# Hall.net
KiCad netlist of a schematic drawn in Altium Designer
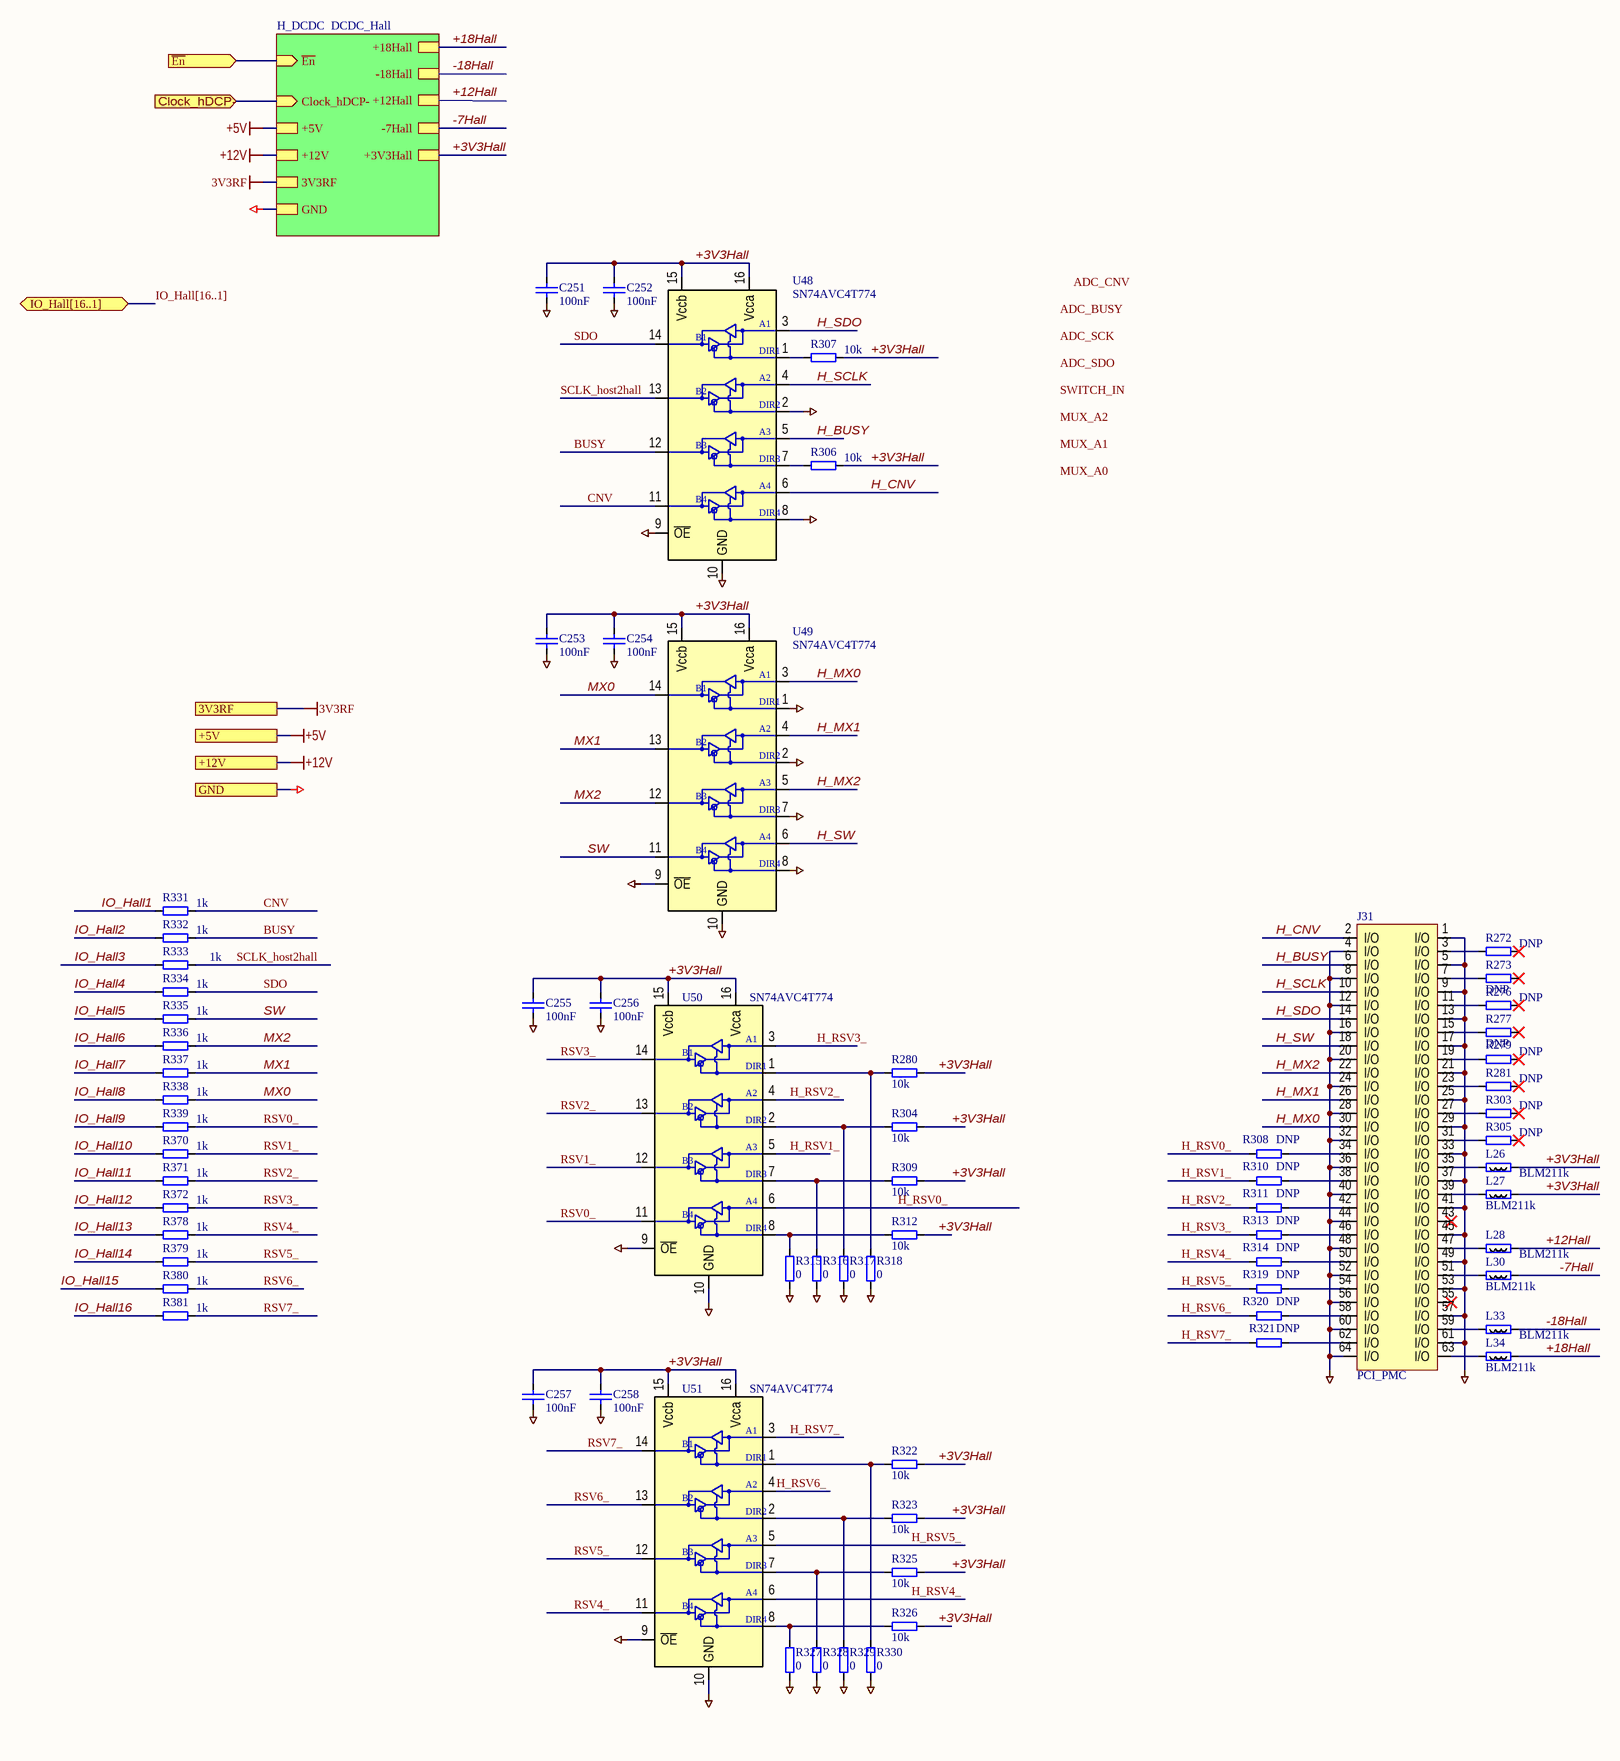
[diagram p0: Hall.SchDoc]

(export (version "E")
  (design (tool "Eeschema 10.0.6"))
  (components
    (comp (ref "C251")
      (value "100nF")
      (footprint "SMD0805CAP")
      (description "Чип конденсатор 0805")
      (fields (field (name "VOLTAGE") "25V") (field (name "TOLERANCE") "20%"))
      (libsource (lib "DDSintLib") (part "C0805"))
    )
    (comp (ref "C252")
      (value "100nF")
      (footprint "SMD0805CAP")
      (description "Чип конденсатор 0805")
      (fields (field (name "VOLTAGE") "25V") (field (name "TOLERANCE") "20%"))
      (libsource (lib "DDSintLib") (part "C0805"))
    )
    (comp (ref "C253")
      (value "100nF")
      (footprint "SMD0805CAP")
      (description "Чип конденсатор 0805")
      (fields (field (name "VOLTAGE") "25V") (field (name "TOLERANCE") "20%"))
      (libsource (lib "DDSintLib") (part "C0805"))
    )
    (comp (ref "C254")
      (value "100nF")
      (footprint "SMD0805CAP")
      (description "Чип конденсатор 0805")
      (fields (field (name "VOLTAGE") "25V") (field (name "TOLERANCE") "20%"))
      (libsource (lib "DDSintLib") (part "C0805"))
    )
    (comp (ref "C255")
      (value "100nF")
      (footprint "SMD0805CAP")
      (description "Чип конденсатор 0805")
      (fields (field (name "VOLTAGE") "25V") (field (name "TOLERANCE") "20%"))
      (libsource (lib "DDSintLib") (part "C0805"))
    )
    (comp (ref "C256")
      (value "100nF")
      (footprint "SMD0805CAP")
      (description "Чип конденсатор 0805")
      (fields (field (name "VOLTAGE") "25V") (field (name "TOLERANCE") "20%"))
      (libsource (lib "DDSintLib") (part "C0805"))
    )
    (comp (ref "C257")
      (value "100nF")
      (footprint "SMD0805CAP")
      (description "Чип конденсатор 0805")
      (fields (field (name "VOLTAGE") "25V") (field (name "TOLERANCE") "20%"))
      (libsource (lib "DDSintLib") (part "C0805"))
    )
    (comp (ref "C258")
      (value "100nF")
      (footprint "SMD0805CAP")
      (description "Чип конденсатор 0805")
      (fields (field (name "VOLTAGE") "25V") (field (name "TOLERANCE") "20%"))
      (libsource (lib "DDSintLib") (part "C0805"))
    )
    (comp (ref "J31")
      (value "PCI_PMC")
      (footprint "TYCO_120521-1")
      (description "PCI Mezzanine Connector; IEEE 1386 MainBoard")
      (libsource (lib "DDSintLib") (part "PCI_PMC_M"))
    )
    (comp (ref "L26")
      (value "BLM211k")
      (footprint "RESC2012X50N")
      (description "SMD Ferrite bead 0805")
      (libsource (lib "DDSintLib") (part "BLM21"))
    )
    (comp (ref "L27")
      (value "BLM211k")
      (footprint "RESC2012X50N")
      (description "SMD Ferrite bead 0805")
      (libsource (lib "DDSintLib") (part "BLM21"))
    )
    (comp (ref "L28")
      (value "BLM211k")
      (footprint "RESC2012X50N")
      (description "SMD Ferrite bead 0805")
      (libsource (lib "DDSintLib") (part "BLM21"))
    )
    (comp (ref "L30")
      (value "BLM211k")
      (footprint "RESC2012X50N")
      (description "SMD Ferrite bead 0805")
      (libsource (lib "DDSintLib") (part "BLM21"))
    )
    (comp (ref "L33")
      (value "BLM211k")
      (footprint "RESC2012X50N")
      (description "SMD Ferrite bead 0805")
      (libsource (lib "DDSintLib") (part "BLM21"))
    )
    (comp (ref "L34")
      (value "BLM211k")
      (footprint "RESC2012X50N")
      (description "SMD Ferrite bead 0805")
      (libsource (lib "DDSintLib") (part "BLM21"))
    )
    (comp (ref "R272")
      (value "DNP")
      (footprint "SMD0805RES")
      (description "Чип резистор 0805")
      (fields (field (name "TOLERANCE") "1%"))
      (libsource (lib "DDSintLib") (part "R0805"))
    )
    (comp (ref "R273")
      (value "DNP")
      (footprint "SMD0805RES")
      (description "Чип резистор 0805")
      (fields (field (name "TOLERANCE") "1%"))
      (libsource (lib "DDSintLib") (part "R0805"))
    )
    (comp (ref "R276")
      (value "DNP")
      (footprint "SMD0805RES")
      (description "Чип резистор 0805")
      (fields (field (name "TOLERANCE") "1%"))
      (libsource (lib "DDSintLib") (part "R0805"))
    )
    (comp (ref "R277")
      (value "DNP")
      (footprint "SMD0805RES")
      (description "Чип резистор 0805")
      (fields (field (name "TOLERANCE") "1%"))
      (libsource (lib "DDSintLib") (part "R0805"))
    )
    (comp (ref "R279")
      (value "DNP")
      (footprint "SMD0805RES")
      (description "Чип резистор 0805")
      (fields (field (name "TOLERANCE") "1%"))
      (libsource (lib "DDSintLib") (part "R0805"))
    )
    (comp (ref "R280")
      (value "10k")
      (footprint "SMD0805RES")
      (description "Чип резистор 0805")
      (fields (field (name "TOLERANCE") "1%"))
      (libsource (lib "DDSintLib") (part "R0805"))
    )
    (comp (ref "R281")
      (value "DNP")
      (footprint "SMD0805RES")
      (description "Чип резистор 0805")
      (fields (field (name "TOLERANCE") "1%"))
      (libsource (lib "DDSintLib") (part "R0805"))
    )
    (comp (ref "R303")
      (value "DNP")
      (footprint "SMD0805RES")
      (description "Чип резистор 0805")
      (fields (field (name "TOLERANCE") "1%"))
      (libsource (lib "DDSintLib") (part "R0805"))
    )
    (comp (ref "R304")
      (value "10k")
      (footprint "SMD0805RES")
      (description "Чип резистор 0805")
      (fields (field (name "TOLERANCE") "1%"))
      (libsource (lib "DDSintLib") (part "R0805"))
    )
    (comp (ref "R305")
      (value "DNP")
      (footprint "SMD0805RES")
      (description "Чип резистор 0805")
      (fields (field (name "TOLERANCE") "1%"))
      (libsource (lib "DDSintLib") (part "R0805"))
    )
    (comp (ref "R306")
      (value "10k")
      (footprint "SMD0805RES")
      (description "Чип резистор 0805")
      (fields (field (name "TOLERANCE") "1%"))
      (libsource (lib "DDSintLib") (part "R0805"))
    )
    (comp (ref "R307")
      (value "10k")
      (footprint "SMD0805RES")
      (description "Чип резистор 0805")
      (fields (field (name "TOLERANCE") "1%"))
      (libsource (lib "DDSintLib") (part "R0805"))
    )
    (comp (ref "R308")
      (value "DNP")
      (footprint "SMD0805RES")
      (description "Чип резистор 0805")
      (fields (field (name "TOLERANCE") "1%"))
      (libsource (lib "DDSintLib") (part "R0805"))
    )
    (comp (ref "R309")
      (value "10k")
      (footprint "SMD0805RES")
      (description "Чип резистор 0805")
      (fields (field (name "TOLERANCE") "1%"))
      (libsource (lib "DDSintLib") (part "R0805"))
    )
    (comp (ref "R310")
      (value "DNP")
      (footprint "SMD0805RES")
      (description "Чип резистор 0805")
      (fields (field (name "TOLERANCE") "1%"))
      (libsource (lib "DDSintLib") (part "R0805"))
    )
    (comp (ref "R311")
      (value "DNP")
      (footprint "SMD0805RES")
      (description "Чип резистор 0805")
      (fields (field (name "TOLERANCE") "1%"))
      (libsource (lib "DDSintLib") (part "R0805"))
    )
    (comp (ref "R312")
      (value "10k")
      (footprint "SMD0805RES")
      (description "Чип резистор 0805")
      (fields (field (name "TOLERANCE") "1%"))
      (libsource (lib "DDSintLib") (part "R0805"))
    )
    (comp (ref "R313")
      (value "DNP")
      (footprint "SMD0805RES")
      (description "Чип резистор 0805")
      (fields (field (name "TOLERANCE") "1%"))
      (libsource (lib "DDSintLib") (part "R0805"))
    )
    (comp (ref "R314")
      (value "DNP")
      (footprint "SMD0805RES")
      (description "Чип резистор 0805")
      (fields (field (name "TOLERANCE") "1%"))
      (libsource (lib "DDSintLib") (part "R0805"))
    )
    (comp (ref "R315")
      (value "0")
      (footprint "SMD0805RES")
      (description "Чип резистор 0805")
      (fields (field (name "TOLERANCE") "1%"))
      (libsource (lib "DDSintLib") (part "R0805"))
    )
    (comp (ref "R316")
      (value "0")
      (footprint "SMD0805RES")
      (description "Чип резистор 0805")
      (fields (field (name "TOLERANCE") "1%"))
      (libsource (lib "DDSintLib") (part "R0805"))
    )
    (comp (ref "R317")
      (value "0")
      (footprint "SMD0805RES")
      (description "Чип резистор 0805")
      (fields (field (name "TOLERANCE") "1%"))
      (libsource (lib "DDSintLib") (part "R0805"))
    )
    (comp (ref "R318")
      (value "0")
      (footprint "SMD0805RES")
      (description "Чип резистор 0805")
      (fields (field (name "TOLERANCE") "1%"))
      (libsource (lib "DDSintLib") (part "R0805"))
    )
    (comp (ref "R319")
      (value "DNP")
      (footprint "SMD0805RES")
      (description "Чип резистор 0805")
      (fields (field (name "TOLERANCE") "1%"))
      (libsource (lib "DDSintLib") (part "R0805"))
    )
    (comp (ref "R320")
      (value "DNP")
      (footprint "SMD0805RES")
      (description "Чип резистор 0805")
      (fields (field (name "TOLERANCE") "1%"))
      (libsource (lib "DDSintLib") (part "R0805"))
    )
    (comp (ref "R321")
      (value "DNP")
      (footprint "SMD0805RES")
      (description "Чип резистор 0805")
      (fields (field (name "TOLERANCE") "1%"))
      (libsource (lib "DDSintLib") (part "R0805"))
    )
    (comp (ref "R322")
      (value "10k")
      (footprint "SMD0805RES")
      (description "Чип резистор 0805")
      (fields (field (name "TOLERANCE") "1%"))
      (libsource (lib "DDSintLib") (part "R0805"))
    )
    (comp (ref "R323")
      (value "10k")
      (footprint "SMD0805RES")
      (description "Чип резистор 0805")
      (fields (field (name "TOLERANCE") "1%"))
      (libsource (lib "DDSintLib") (part "R0805"))
    )
    (comp (ref "R325")
      (value "10k")
      (footprint "SMD0805RES")
      (description "Чип резистор 0805")
      (fields (field (name "TOLERANCE") "1%"))
      (libsource (lib "DDSintLib") (part "R0805"))
    )
    (comp (ref "R326")
      (value "10k")
      (footprint "SMD0805RES")
      (description "Чип резистор 0805")
      (fields (field (name "TOLERANCE") "1%"))
      (libsource (lib "DDSintLib") (part "R0805"))
    )
    (comp (ref "R327")
      (value "0")
      (footprint "SMD0805RES")
      (description "Чип резистор 0805")
      (fields (field (name "TOLERANCE") "1%"))
      (libsource (lib "DDSintLib") (part "R0805"))
    )
    (comp (ref "R328")
      (value "0")
      (footprint "SMD0805RES")
      (description "Чип резистор 0805")
      (fields (field (name "TOLERANCE") "1%"))
      (libsource (lib "DDSintLib") (part "R0805"))
    )
    (comp (ref "R329")
      (value "0")
      (footprint "SMD0805RES")
      (description "Чип резистор 0805")
      (fields (field (name "TOLERANCE") "1%"))
      (libsource (lib "DDSintLib") (part "R0805"))
    )
    (comp (ref "R330")
      (value "0")
      (footprint "SMD0805RES")
      (description "Чип резистор 0805")
      (fields (field (name "TOLERANCE") "1%"))
      (libsource (lib "DDSintLib") (part "R0805"))
    )
    (comp (ref "R331")
      (value "1k")
      (footprint "SMD0805RES")
      (description "Чип резистор 0805")
      (fields (field (name "TOLERANCE") "1%"))
      (libsource (lib "DDSintLib") (part "R0805"))
    )
    (comp (ref "R332")
      (value "1k")
      (footprint "SMD0805RES")
      (description "Чип резистор 0805")
      (fields (field (name "TOLERANCE") "1%"))
      (libsource (lib "DDSintLib") (part "R0805"))
    )
    (comp (ref "R333")
      (value "1k")
      (footprint "SMD0805RES")
      (description "Чип резистор 0805")
      (fields (field (name "TOLERANCE") "1%"))
      (libsource (lib "DDSintLib") (part "R0805"))
    )
    (comp (ref "R334")
      (value "1k")
      (footprint "SMD0805RES")
      (description "Чип резистор 0805")
      (fields (field (name "TOLERANCE") "1%"))
      (libsource (lib "DDSintLib") (part "R0805"))
    )
    (comp (ref "R335")
      (value "1k")
      (footprint "SMD0805RES")
      (description "Чип резистор 0805")
      (fields (field (name "TOLERANCE") "1%"))
      (libsource (lib "DDSintLib") (part "R0805"))
    )
    (comp (ref "R336")
      (value "1k")
      (footprint "SMD0805RES")
      (description "Чип резистор 0805")
      (fields (field (name "TOLERANCE") "1%"))
      (libsource (lib "DDSintLib") (part "R0805"))
    )
    (comp (ref "R337")
      (value "1k")
      (footprint "SMD0805RES")
      (description "Чип резистор 0805")
      (fields (field (name "TOLERANCE") "1%"))
      (libsource (lib "DDSintLib") (part "R0805"))
    )
    (comp (ref "R338")
      (value "1k")
      (footprint "SMD0805RES")
      (description "Чип резистор 0805")
      (fields (field (name "TOLERANCE") "1%"))
      (libsource (lib "DDSintLib") (part "R0805"))
    )
    (comp (ref "R339")
      (value "1k")
      (footprint "SMD0805RES")
      (description "Чип резистор 0805")
      (fields (field (name "TOLERANCE") "1%"))
      (libsource (lib "DDSintLib") (part "R0805"))
    )
    (comp (ref "R370")
      (value "1k")
      (footprint "SMD0805RES")
      (description "Чип резистор 0805")
      (fields (field (name "TOLERANCE") "1%"))
      (libsource (lib "DDSintLib") (part "R0805"))
    )
    (comp (ref "R371")
      (value "1k")
      (footprint "SMD0805RES")
      (description "Чип резистор 0805")
      (fields (field (name "TOLERANCE") "1%"))
      (libsource (lib "DDSintLib") (part "R0805"))
    )
    (comp (ref "R372")
      (value "1k")
      (footprint "SMD0805RES")
      (description "Чип резистор 0805")
      (fields (field (name "TOLERANCE") "1%"))
      (libsource (lib "DDSintLib") (part "R0805"))
    )
    (comp (ref "R378")
      (value "1k")
      (footprint "SMD0805RES")
      (description "Чип резистор 0805")
      (fields (field (name "TOLERANCE") "1%"))
      (libsource (lib "DDSintLib") (part "R0805"))
    )
    (comp (ref "R379")
      (value "1k")
      (footprint "SMD0805RES")
      (description "Чип резистор 0805")
      (fields (field (name "TOLERANCE") "1%"))
      (libsource (lib "DDSintLib") (part "R0805"))
    )
    (comp (ref "R380")
      (value "1k")
      (footprint "SMD0805RES")
      (description "Чип резистор 0805")
      (fields (field (name "TOLERANCE") "1%"))
      (libsource (lib "DDSintLib") (part "R0805"))
    )
    (comp (ref "R381")
      (value "1k")
      (footprint "SMD0805RES")
      (description "Чип резистор 0805")
      (fields (field (name "TOLERANCE") "1%"))
      (libsource (lib "DDSintLib") (part "R0805"))
    )
    (comp (ref "U48")
      (value "SN74AVC4T774")
      (footprint "TSSOP-16")
      (description "Двунаправленный буфер")
      (fields (field (name "VOLTAGE") "1V1.. 3.6V  I/Os are 4.6-V Tolerant"))
      (libsource (lib "DDS1") (part "SN74AVC4T774"))
    )
    (comp (ref "U49")
      (value "SN74AVC4T774")
      (footprint "TSSOP-16")
      (description "Двунаправленный буфер")
      (fields (field (name "VOLTAGE") "1V1.. 3.6V  I/Os are 4.6-V Tolerant"))
      (libsource (lib "DDS1") (part "SN74AVC4T774"))
    )
    (comp (ref "U50")
      (value "SN74AVC4T774")
      (footprint "TSSOP-16")
      (description "Двунаправленный буфер")
      (fields (field (name "VOLTAGE") "1V1.. 3.6V  I/Os are 4.6-V Tolerant"))
      (libsource (lib "DDS1") (part "SN74AVC4T774"))
    )
    (comp (ref "U51")
      (value "SN74AVC4T774")
      (footprint "TSSOP-16")
      (description "Двунаправленный буфер")
      (fields (field (name "VOLTAGE") "1V1.. 3.6V  I/Os are 4.6-V Tolerant"))
      (libsource (lib "DDS1") (part "SN74AVC4T774"))
    )
  )
  (nets
    (net (code "3") (name "/+3V3Hall") (class "Default")
      (node (ref "C251") (pin "2") (pinfunction "2_2") (pintype "passive"))
      (node (ref "C252") (pin "2") (pinfunction "2_2") (pintype "passive"))
      (node (ref "C253") (pin "2") (pinfunction "2_2") (pintype "passive"))
      (node (ref "C254") (pin "2") (pinfunction "2_2") (pintype "passive"))
      (node (ref "C255") (pin "2") (pinfunction "2_2") (pintype "passive"))
      (node (ref "C256") (pin "2") (pinfunction "2_2") (pintype "passive"))
      (node (ref "C257") (pin "2") (pinfunction "2_2") (pintype "passive"))
      (node (ref "C258") (pin "2") (pinfunction "2_2") (pintype "passive"))
      (node (ref "L26") (pin "2") (pinfunction "2_2") (pintype "passive"))
      (node (ref "L27") (pin "2") (pinfunction "2_2") (pintype "passive"))
      (node (ref "R280") (pin "2") (pinfunction "2_2") (pintype "passive"))
      (node (ref "R304") (pin "2") (pinfunction "2_2") (pintype "passive"))
      (node (ref "R306") (pin "1") (pinfunction "1_1") (pintype "passive"))
      (node (ref "R307") (pin "1") (pinfunction "1_1") (pintype "passive"))
      (node (ref "R309") (pin "2") (pinfunction "2_2") (pintype "passive"))
      (node (ref "R312") (pin "2") (pinfunction "2_2") (pintype "passive"))
      (node (ref "R322") (pin "2") (pinfunction "2_2") (pintype "passive"))
      (node (ref "R323") (pin "2") (pinfunction "2_2") (pintype "passive"))
      (node (ref "R325") (pin "2") (pinfunction "2_2") (pintype "passive"))
      (node (ref "R326") (pin "2") (pinfunction "2_2") (pintype "passive"))
      (node (ref "U48") (pin "15") (pinfunction "Vccb_15") (pintype "passive"))
      (node (ref "U48") (pin "16") (pinfunction "Vcca_16") (pintype "passive"))
      (node (ref "U49") (pin "15") (pinfunction "Vccb_15") (pintype "passive"))
      (node (ref "U49") (pin "16") (pinfunction "Vcca_16") (pintype "passive"))
      (node (ref "U50") (pin "15") (pinfunction "Vccb_15") (pintype "passive"))
      (node (ref "U50") (pin "16") (pinfunction "Vcca_16") (pintype "passive"))
      (node (ref "U51") (pin "15") (pinfunction "Vccb_15") (pintype "passive"))
      (node (ref "U51") (pin "16") (pinfunction "Vcca_16") (pintype "passive"))
    )
    (net (code "4") (name "/+12Hall") (class "Default")
      (node (ref "L28") (pin "2") (pinfunction "2_2") (pintype "passive"))
    )
    (net (code "6") (name "/+18Hall") (class "Default")
      (node (ref "L34") (pin "2") (pinfunction "2_2") (pintype "passive"))
    )
    (net (code "7") (name "/-7Hall") (class "Default")
      (node (ref "L30") (pin "2") (pinfunction "2_2") (pintype "passive"))
    )
    (net (code "8") (name "/-18Hall") (class "Default")
      (node (ref "L33") (pin "2") (pinfunction "2_2") (pintype "passive"))
    )
    (net (code "14") (name "/BUSY") (class "Default")
      (node (ref "R332") (pin "1") (pinfunction "1_1") (pintype "passive"))
      (node (ref "U48") (pin "12") (pinfunction "B3_12") (pintype "passive"))
    )
    (net (code "15") (name "/CNV") (class "Default")
      (node (ref "R331") (pin "1") (pinfunction "1_1") (pintype "passive"))
      (node (ref "U48") (pin "11") (pinfunction "B4_11") (pintype "passive"))
    )
    (net (code "18") (name "/H_BUSY") (class "Default")
      (node (ref "J31") (pin "6") (pinfunction "I/O_6") (pintype "bidirectional"))
      (node (ref "U48") (pin "5") (pinfunction "A3_5") (pintype "passive"))
    )
    (net (code "19") (name "/H_CNV") (class "Default")
      (node (ref "J31") (pin "2") (pinfunction "I/O_2") (pintype "bidirectional"))
      (node (ref "U48") (pin "6") (pinfunction "A4_6") (pintype "passive"))
    )
    (net (code "20") (name "/H_MX0") (class "Default")
      (node (ref "J31") (pin "30") (pinfunction "I/O_30") (pintype "bidirectional"))
      (node (ref "U49") (pin "3") (pinfunction "A1_3") (pintype "passive"))
    )
    (net (code "21") (name "/H_MX1") (class "Default")
      (node (ref "J31") (pin "26") (pinfunction "I/O_26") (pintype "bidirectional"))
      (node (ref "U49") (pin "4") (pinfunction "A2_4") (pintype "passive"))
    )
    (net (code "22") (name "/H_MX2") (class "Default")
      (node (ref "J31") (pin "22") (pinfunction "I/O_22") (pintype "bidirectional"))
      (node (ref "U49") (pin "5") (pinfunction "A3_5") (pintype "passive"))
    )
    (net (code "23") (name "/H_RSV0_") (class "Default")
      (node (ref "R308") (pin "2") (pinfunction "2_2") (pintype "passive"))
      (node (ref "U50") (pin "6") (pinfunction "A4_6") (pintype "passive"))
    )
    (net (code "24") (name "/H_RSV1_") (class "Default")
      (node (ref "R310") (pin "2") (pinfunction "2_2") (pintype "passive"))
      (node (ref "U50") (pin "5") (pinfunction "A3_5") (pintype "passive"))
    )
    (net (code "25") (name "/H_RSV2_") (class "Default")
      (node (ref "R311") (pin "2") (pinfunction "2_2") (pintype "passive"))
      (node (ref "U50") (pin "4") (pinfunction "A2_4") (pintype "passive"))
    )
    (net (code "26") (name "/H_RSV3_") (class "Default")
      (node (ref "R313") (pin "2") (pinfunction "2_2") (pintype "passive"))
      (node (ref "U50") (pin "3") (pinfunction "A1_3") (pintype "passive"))
    )
    (net (code "27") (name "/H_RSV4_") (class "Default")
      (node (ref "R314") (pin "2") (pinfunction "2_2") (pintype "passive"))
      (node (ref "U51") (pin "6") (pinfunction "A4_6") (pintype "passive"))
    )
    (net (code "28") (name "/H_RSV5_") (class "Default")
      (node (ref "R319") (pin "2") (pinfunction "2_2") (pintype "passive"))
      (node (ref "U51") (pin "5") (pinfunction "A3_5") (pintype "passive"))
    )
    (net (code "29") (name "/H_RSV6_") (class "Default")
      (node (ref "R320") (pin "2") (pinfunction "2_2") (pintype "passive"))
      (node (ref "U51") (pin "4") (pinfunction "A2_4") (pintype "passive"))
    )
    (net (code "30") (name "/H_RSV7_") (class "Default")
      (node (ref "R321") (pin "2") (pinfunction "2_2") (pintype "passive"))
      (node (ref "U51") (pin "3") (pinfunction "A1_3") (pintype "passive"))
    )
    (net (code "31") (name "/H_SCLK") (class "Default")
      (node (ref "J31") (pin "10") (pinfunction "I/O_10") (pintype "bidirectional"))
      (node (ref "U48") (pin "4") (pinfunction "A2_4") (pintype "passive"))
    )
    (net (code "32") (name "/H_SDO") (class "Default")
      (node (ref "J31") (pin "14") (pinfunction "I/O_14") (pintype "bidirectional"))
      (node (ref "U48") (pin "3") (pinfunction "A1_3") (pintype "passive"))
    )
    (net (code "33") (name "/H_SW") (class "Default")
      (node (ref "J31") (pin "18") (pinfunction "I/O_18") (pintype "bidirectional"))
      (node (ref "U49") (pin "6") (pinfunction "A4_6") (pintype "passive"))
    )
    (net (code "34") (name "/IO_Hall1") (class "Default")
      (node (ref "R331") (pin "2") (pinfunction "2_2") (pintype "passive"))
    )
    (net (code "35") (name "/IO_Hall2") (class "Default")
      (node (ref "R332") (pin "2") (pinfunction "2_2") (pintype "passive"))
    )
    (net (code "36") (name "/IO_Hall3") (class "Default")
      (node (ref "R333") (pin "2") (pinfunction "2_2") (pintype "passive"))
    )
    (net (code "37") (name "/IO_Hall4") (class "Default")
      (node (ref "R334") (pin "2") (pinfunction "2_2") (pintype "passive"))
    )
    (net (code "38") (name "/IO_Hall5") (class "Default")
      (node (ref "R335") (pin "2") (pinfunction "2_2") (pintype "passive"))
    )
    (net (code "39") (name "/IO_Hall6") (class "Default")
      (node (ref "R336") (pin "2") (pinfunction "2_2") (pintype "passive"))
    )
    (net (code "40") (name "/IO_Hall7") (class "Default")
      (node (ref "R337") (pin "2") (pinfunction "2_2") (pintype "passive"))
    )
    (net (code "41") (name "/IO_Hall8") (class "Default")
      (node (ref "R338") (pin "2") (pinfunction "2_2") (pintype "passive"))
    )
    (net (code "42") (name "/IO_Hall9") (class "Default")
      (node (ref "R339") (pin "2") (pinfunction "2_2") (pintype "passive"))
    )
    (net (code "43") (name "/IO_Hall10") (class "Default")
      (node (ref "R370") (pin "2") (pinfunction "2_2") (pintype "passive"))
    )
    (net (code "44") (name "/IO_Hall11") (class "Default")
      (node (ref "R371") (pin "2") (pinfunction "2_2") (pintype "passive"))
    )
    (net (code "45") (name "/IO_Hall12") (class "Default")
      (node (ref "R372") (pin "2") (pinfunction "2_2") (pintype "passive"))
    )
    (net (code "46") (name "/IO_Hall13") (class "Default")
      (node (ref "R378") (pin "2") (pinfunction "2_2") (pintype "passive"))
    )
    (net (code "47") (name "/IO_Hall14") (class "Default")
      (node (ref "R379") (pin "2") (pinfunction "2_2") (pintype "passive"))
    )
    (net (code "48") (name "/IO_Hall15") (class "Default")
      (node (ref "R380") (pin "2") (pinfunction "2_2") (pintype "passive"))
    )
    (net (code "49") (name "/IO_Hall16") (class "Default")
      (node (ref "R381") (pin "2") (pinfunction "2_2") (pintype "passive"))
    )
    (net (code "54") (name "/MX0") (class "Default")
      (node (ref "R338") (pin "1") (pinfunction "1_1") (pintype "passive"))
      (node (ref "U49") (pin "14") (pinfunction "B1_14") (pintype "passive"))
    )
    (net (code "55") (name "/MX1") (class "Default")
      (node (ref "R337") (pin "1") (pinfunction "1_1") (pintype "passive"))
      (node (ref "U49") (pin "13") (pinfunction "B2_13") (pintype "passive"))
    )
    (net (code "56") (name "/MX2") (class "Default")
      (node (ref "R336") (pin "1") (pinfunction "1_1") (pintype "passive"))
      (node (ref "U49") (pin "12") (pinfunction "B3_12") (pintype "passive"))
    )
    (net (code "57") (name "/RSV0_") (class "Default")
      (node (ref "R339") (pin "1") (pinfunction "1_1") (pintype "passive"))
      (node (ref "U50") (pin "11") (pinfunction "B4_11") (pintype "passive"))
    )
    (net (code "58") (name "/RSV1_") (class "Default")
      (node (ref "R370") (pin "1") (pinfunction "1_1") (pintype "passive"))
      (node (ref "U50") (pin "12") (pinfunction "B3_12") (pintype "passive"))
    )
    (net (code "59") (name "/RSV2_") (class "Default")
      (node (ref "R371") (pin "1") (pinfunction "1_1") (pintype "passive"))
      (node (ref "U50") (pin "13") (pinfunction "B2_13") (pintype "passive"))
    )
    (net (code "60") (name "/RSV3_") (class "Default")
      (node (ref "R372") (pin "1") (pinfunction "1_1") (pintype "passive"))
      (node (ref "U50") (pin "14") (pinfunction "B1_14") (pintype "passive"))
    )
    (net (code "61") (name "/RSV4_") (class "Default")
      (node (ref "R378") (pin "1") (pinfunction "1_1") (pintype "passive"))
      (node (ref "U51") (pin "11") (pinfunction "B4_11") (pintype "passive"))
    )
    (net (code "62") (name "/RSV5_") (class "Default")
      (node (ref "R379") (pin "1") (pinfunction "1_1") (pintype "passive"))
      (node (ref "U51") (pin "12") (pinfunction "B3_12") (pintype "passive"))
    )
    (net (code "63") (name "/RSV6_") (class "Default")
      (node (ref "R380") (pin "1") (pinfunction "1_1") (pintype "passive"))
      (node (ref "U51") (pin "13") (pinfunction "B2_13") (pintype "passive"))
    )
    (net (code "64") (name "/RSV7_") (class "Default")
      (node (ref "R381") (pin "1") (pinfunction "1_1") (pintype "passive"))
      (node (ref "U51") (pin "14") (pinfunction "B1_14") (pintype "passive"))
    )
    (net (code "65") (name "/SCLK_host2hall") (class "Default")
      (node (ref "R333") (pin "1") (pinfunction "1_1") (pintype "passive"))
      (node (ref "U48") (pin "13") (pinfunction "B2_13") (pintype "passive"))
    )
    (net (code "66") (name "/SDO") (class "Default")
      (node (ref "R334") (pin "1") (pinfunction "1_1") (pintype "passive"))
      (node (ref "U48") (pin "14") (pinfunction "B1_14") (pintype "passive"))
    )
    (net (code "67") (name "/SW") (class "Default")
      (node (ref "R335") (pin "1") (pinfunction "1_1") (pintype "passive"))
      (node (ref "U49") (pin "11") (pinfunction "B4_11") (pintype "passive"))
    )
    (net (code "70") (name "GND") (class "Default")
      (node (ref "C251") (pin "1") (pinfunction "1_1") (pintype "passive"))
      (node (ref "C252") (pin "1") (pinfunction "1_1") (pintype "passive"))
      (node (ref "C253") (pin "1") (pinfunction "1_1") (pintype "passive"))
      (node (ref "C254") (pin "1") (pinfunction "1_1") (pintype "passive"))
      (node (ref "C255") (pin "1") (pinfunction "1_1") (pintype "passive"))
      (node (ref "C256") (pin "1") (pinfunction "1_1") (pintype "passive"))
      (node (ref "C257") (pin "1") (pinfunction "1_1") (pintype "passive"))
      (node (ref "C258") (pin "1") (pinfunction "1_1") (pintype "passive"))
      (node (ref "J31") (pin "1") (pinfunction "I/O_1") (pintype "bidirectional"))
      (node (ref "J31") (pin "12") (pinfunction "I/O_12") (pintype "bidirectional"))
      (node (ref "J31") (pin "13") (pinfunction "I/O_13") (pintype "bidirectional"))
      (node (ref "J31") (pin "16") (pinfunction "I/O_16") (pintype "bidirectional"))
      (node (ref "J31") (pin "17") (pinfunction "I/O_17") (pintype "bidirectional"))
      (node (ref "J31") (pin "20") (pinfunction "I/O_20") (pintype "bidirectional"))
      (node (ref "J31") (pin "21") (pinfunction "I/O_21") (pintype "bidirectional"))
      (node (ref "J31") (pin "24") (pinfunction "I/O_24") (pintype "bidirectional"))
      (node (ref "J31") (pin "25") (pinfunction "I/O_25") (pintype "bidirectional"))
      (node (ref "J31") (pin "28") (pinfunction "I/O_28") (pintype "bidirectional"))
      (node (ref "J31") (pin "29") (pinfunction "I/O_29") (pintype "bidirectional"))
      (node (ref "J31") (pin "32") (pinfunction "I/O_32") (pintype "bidirectional"))
      (node (ref "J31") (pin "33") (pinfunction "I/O_33") (pintype "bidirectional"))
      (node (ref "J31") (pin "36") (pinfunction "I/O_36") (pintype "bidirectional"))
      (node (ref "J31") (pin "37") (pinfunction "I/O_37") (pintype "bidirectional"))
      (node (ref "J31") (pin "4") (pinfunction "I/O_4") (pintype "bidirectional"))
      (node (ref "J31") (pin "40") (pinfunction "I/O_40") (pintype "bidirectional"))
      (node (ref "J31") (pin "41") (pinfunction "I/O_41") (pintype "bidirectional"))
      (node (ref "J31") (pin "44") (pinfunction "I/O_44") (pintype "bidirectional"))
      (node (ref "J31") (pin "45") (pinfunction "I/O_45") (pintype "bidirectional"))
      (node (ref "J31") (pin "48") (pinfunction "I/O_48") (pintype "bidirectional"))
      (node (ref "J31") (pin "49") (pinfunction "I/O_49") (pintype "bidirectional"))
      (node (ref "J31") (pin "5") (pinfunction "I/O_5") (pintype "bidirectional"))
      (node (ref "J31") (pin "52") (pinfunction "I/O_52") (pintype "bidirectional"))
      (node (ref "J31") (pin "53") (pinfunction "I/O_53") (pintype "bidirectional"))
      (node (ref "J31") (pin "56") (pinfunction "I/O_56") (pintype "bidirectional"))
      (node (ref "J31") (pin "57") (pinfunction "I/O_57") (pintype "bidirectional"))
      (node (ref "J31") (pin "60") (pinfunction "I/O_60") (pintype "bidirectional"))
      (node (ref "J31") (pin "61") (pinfunction "I/O_61") (pintype "bidirectional"))
      (node (ref "J31") (pin "64") (pinfunction "I/O_64") (pintype "bidirectional"))
      (node (ref "J31") (pin "8") (pinfunction "I/O_8") (pintype "bidirectional"))
      (node (ref "J31") (pin "9") (pinfunction "I/O_9") (pintype "bidirectional"))
      (node (ref "R315") (pin "1") (pinfunction "1_1") (pintype "passive"))
      (node (ref "R316") (pin "1") (pinfunction "1_1") (pintype "passive"))
      (node (ref "R317") (pin "1") (pinfunction "1_1") (pintype "passive"))
      (node (ref "R318") (pin "1") (pinfunction "1_1") (pintype "passive"))
      (node (ref "R327") (pin "1") (pinfunction "1_1") (pintype "passive"))
      (node (ref "R328") (pin "1") (pinfunction "1_1") (pintype "passive"))
      (node (ref "R329") (pin "1") (pinfunction "1_1") (pintype "passive"))
      (node (ref "R330") (pin "1") (pinfunction "1_1") (pintype "passive"))
      (node (ref "U48") (pin "10") (pinfunction "GND_10") (pintype "passive"))
      (node (ref "U48") (pin "2") (pinfunction "DIR2_2") (pintype "passive"))
      (node (ref "U48") (pin "8") (pinfunction "DIR4_8") (pintype "passive"))
      (node (ref "U48") (pin "9") (pinfunction "~{OE}_9") (pintype "passive"))
      (node (ref "U49") (pin "1") (pinfunction "DIR1_1") (pintype "passive"))
      (node (ref "U49") (pin "10") (pinfunction "GND_10") (pintype "passive"))
      (node (ref "U49") (pin "2") (pinfunction "DIR2_2") (pintype "passive"))
      (node (ref "U49") (pin "7") (pinfunction "DIR3_7") (pintype "passive"))
      (node (ref "U49") (pin "8") (pinfunction "DIR4_8") (pintype "passive"))
      (node (ref "U49") (pin "9") (pinfunction "~{OE}_9") (pintype "passive"))
      (node (ref "U50") (pin "10") (pinfunction "GND_10") (pintype "passive"))
      (node (ref "U50") (pin "9") (pinfunction "~{OE}_9") (pintype "passive"))
      (node (ref "U51") (pin "10") (pinfunction "GND_10") (pintype "passive"))
      (node (ref "U51") (pin "9") (pinfunction "~{OE}_9") (pintype "passive"))
    )
    (net (code "71") (name "Net-(J31-I{slash}O-Pad3)") (class "Default")
      (node (ref "J31") (pin "3") (pinfunction "I/O_3") (pintype "bidirectional"))
      (node (ref "R272") (pin "2") (pinfunction "2_2") (pintype "passive"))
    )
    (net (code "72") (name "Net-(J31-I{slash}O-Pad7)") (class "Default")
      (node (ref "J31") (pin "7") (pinfunction "I/O_7") (pintype "bidirectional"))
      (node (ref "R273") (pin "1") (pinfunction "1_1") (pintype "passive"))
    )
    (net (code "73") (name "Net-(J31-I{slash}O-Pad11)") (class "Default")
      (node (ref "J31") (pin "11") (pinfunction "I/O_11") (pintype "bidirectional"))
      (node (ref "R276") (pin "2") (pinfunction "2_2") (pintype "passive"))
    )
    (net (code "74") (name "Net-(J31-I{slash}O-Pad15)") (class "Default")
      (node (ref "J31") (pin "15") (pinfunction "I/O_15") (pintype "bidirectional"))
      (node (ref "R277") (pin "1") (pinfunction "1_1") (pintype "passive"))
    )
    (net (code "75") (name "Net-(J31-I{slash}O-Pad19)") (class "Default")
      (node (ref "J31") (pin "19") (pinfunction "I/O_19") (pintype "bidirectional"))
      (node (ref "R279") (pin "2") (pinfunction "2_2") (pintype "passive"))
    )
    (net (code "76") (name "Net-(J31-I{slash}O-Pad23)") (class "Default")
      (node (ref "J31") (pin "23") (pinfunction "I/O_23") (pintype "bidirectional"))
      (node (ref "R281") (pin "2") (pinfunction "2_2") (pintype "passive"))
    )
    (net (code "77") (name "Net-(J31-I{slash}O-Pad27)") (class "Default")
      (node (ref "J31") (pin "27") (pinfunction "I/O_27") (pintype "bidirectional"))
      (node (ref "R303") (pin "2") (pinfunction "2_2") (pintype "passive"))
    )
    (net (code "78") (name "Net-(J31-I{slash}O-Pad31)") (class "Default")
      (node (ref "J31") (pin "31") (pinfunction "I/O_31") (pintype "bidirectional"))
      (node (ref "R305") (pin "2") (pinfunction "2_2") (pintype "passive"))
    )
    (net (code "79") (name "Net-(J31-I{slash}O-Pad34)") (class "Default")
      (node (ref "J31") (pin "34") (pinfunction "I/O_34") (pintype "bidirectional"))
      (node (ref "R308") (pin "1") (pinfunction "1_1") (pintype "passive"))
    )
    (net (code "80") (name "Net-(J31-I{slash}O-Pad35)") (class "Default")
      (node (ref "J31") (pin "35") (pinfunction "I/O_35") (pintype "bidirectional"))
      (node (ref "L26") (pin "1") (pinfunction "1_1") (pintype "passive"))
    )
    (net (code "81") (name "Net-(J31-I{slash}O-Pad38)") (class "Default")
      (node (ref "J31") (pin "38") (pinfunction "I/O_38") (pintype "bidirectional"))
      (node (ref "R310") (pin "1") (pinfunction "1_1") (pintype "passive"))
    )
    (net (code "82") (name "Net-(J31-I{slash}O-Pad39)") (class "Default")
      (node (ref "J31") (pin "39") (pinfunction "I/O_39") (pintype "bidirectional"))
      (node (ref "L27") (pin "1") (pinfunction "1_1") (pintype "passive"))
    )
    (net (code "83") (name "Net-(J31-I{slash}O-Pad42)") (class "Default")
      (node (ref "J31") (pin "42") (pinfunction "I/O_42") (pintype "bidirectional"))
      (node (ref "R311") (pin "1") (pinfunction "1_1") (pintype "passive"))
    )
    (net (code "84") (name "Net-(J31-I{slash}O-Pad46)") (class "Default")
      (node (ref "J31") (pin "46") (pinfunction "I/O_46") (pintype "bidirectional"))
      (node (ref "R313") (pin "1") (pinfunction "1_1") (pintype "passive"))
    )
    (net (code "85") (name "Net-(J31-I{slash}O-Pad47)") (class "Default")
      (node (ref "J31") (pin "47") (pinfunction "I/O_47") (pintype "bidirectional"))
      (node (ref "L28") (pin "1") (pinfunction "1_1") (pintype "passive"))
    )
    (net (code "86") (name "Net-(J31-I{slash}O-Pad50)") (class "Default")
      (node (ref "J31") (pin "50") (pinfunction "I/O_50") (pintype "bidirectional"))
      (node (ref "R314") (pin "1") (pinfunction "1_1") (pintype "passive"))
    )
    (net (code "87") (name "Net-(J31-I{slash}O-Pad51)") (class "Default")
      (node (ref "J31") (pin "51") (pinfunction "I/O_51") (pintype "bidirectional"))
      (node (ref "L30") (pin "1") (pinfunction "1_1") (pintype "passive"))
    )
    (net (code "88") (name "Net-(J31-I{slash}O-Pad54)") (class "Default")
      (node (ref "J31") (pin "54") (pinfunction "I/O_54") (pintype "bidirectional"))
      (node (ref "R319") (pin "1") (pinfunction "1_1") (pintype "passive"))
    )
    (net (code "89") (name "Net-(J31-I{slash}O-Pad58)") (class "Default")
      (node (ref "J31") (pin "58") (pinfunction "I/O_58") (pintype "bidirectional"))
      (node (ref "R320") (pin "1") (pinfunction "1_1") (pintype "passive"))
    )
    (net (code "90") (name "Net-(J31-I{slash}O-Pad59)") (class "Default")
      (node (ref "J31") (pin "59") (pinfunction "I/O_59") (pintype "bidirectional"))
      (node (ref "L33") (pin "1") (pinfunction "1_1") (pintype "passive"))
    )
    (net (code "91") (name "Net-(J31-I{slash}O-Pad62)") (class "Default")
      (node (ref "J31") (pin "62") (pinfunction "I/O_62") (pintype "bidirectional"))
      (node (ref "R321") (pin "1") (pinfunction "1_1") (pintype "passive"))
    )
    (net (code "92") (name "Net-(J31-I{slash}O-Pad63)") (class "Default")
      (node (ref "J31") (pin "63") (pinfunction "I/O_63") (pintype "bidirectional"))
      (node (ref "L34") (pin "1") (pinfunction "1_1") (pintype "passive"))
    )
    (net (code "93") (name "Net-(U48-DIR1)") (class "Default")
      (node (ref "R307") (pin "2") (pinfunction "2_2") (pintype "passive"))
      (node (ref "U48") (pin "1") (pinfunction "DIR1_1") (pintype "passive"))
    )
    (net (code "94") (name "Net-(U48-DIR3)") (class "Default")
      (node (ref "R306") (pin "2") (pinfunction "2_2") (pintype "passive"))
      (node (ref "U48") (pin "7") (pinfunction "DIR3_7") (pintype "passive"))
    )
    (net (code "95") (name "Net-(U50-DIR1)") (class "Default")
      (node (ref "R280") (pin "1") (pinfunction "1_1") (pintype "passive"))
      (node (ref "R318") (pin "2") (pinfunction "2_2") (pintype "passive"))
      (node (ref "U50") (pin "1") (pinfunction "DIR1_1") (pintype "passive"))
    )
    (net (code "96") (name "Net-(U50-DIR2)") (class "Default")
      (node (ref "R304") (pin "1") (pinfunction "1_1") (pintype "passive"))
      (node (ref "R317") (pin "2") (pinfunction "2_2") (pintype "passive"))
      (node (ref "U50") (pin "2") (pinfunction "DIR2_2") (pintype "passive"))
    )
    (net (code "97") (name "Net-(U50-DIR3)") (class "Default")
      (node (ref "R309") (pin "1") (pinfunction "1_1") (pintype "passive"))
      (node (ref "R316") (pin "2") (pinfunction "2_2") (pintype "passive"))
      (node (ref "U50") (pin "7") (pinfunction "DIR3_7") (pintype "passive"))
    )
    (net (code "98") (name "Net-(U50-DIR4)") (class "Default")
      (node (ref "R312") (pin "1") (pinfunction "1_1") (pintype "passive"))
      (node (ref "R315") (pin "2") (pinfunction "2_2") (pintype "passive"))
      (node (ref "U50") (pin "8") (pinfunction "DIR4_8") (pintype "passive"))
    )
    (net (code "99") (name "Net-(U51-DIR1)") (class "Default")
      (node (ref "R322") (pin "1") (pinfunction "1_1") (pintype "passive"))
      (node (ref "R330") (pin "2") (pinfunction "2_2") (pintype "passive"))
      (node (ref "U51") (pin "1") (pinfunction "DIR1_1") (pintype "passive"))
    )
    (net (code "100") (name "Net-(U51-DIR2)") (class "Default")
      (node (ref "R323") (pin "1") (pinfunction "1_1") (pintype "passive"))
      (node (ref "R329") (pin "2") (pinfunction "2_2") (pintype "passive"))
      (node (ref "U51") (pin "2") (pinfunction "DIR2_2") (pintype "passive"))
    )
    (net (code "101") (name "Net-(U51-DIR3)") (class "Default")
      (node (ref "R325") (pin "1") (pinfunction "1_1") (pintype "passive"))
      (node (ref "R328") (pin "2") (pinfunction "2_2") (pintype "passive"))
      (node (ref "U51") (pin "7") (pinfunction "DIR3_7") (pintype "passive"))
    )
    (net (code "102") (name "Net-(U51-DIR4)") (class "Default")
      (node (ref "R326") (pin "1") (pinfunction "1_1") (pintype "passive"))
      (node (ref "R327") (pin "2") (pinfunction "2_2") (pintype "passive"))
      (node (ref "U51") (pin "8") (pinfunction "DIR4_8") (pintype "passive"))
    )
    (net (code "103") (name "unconnected-(J31-I{slash}O-Pad43)") (class "Default")
      (node (ref "J31") (pin "43") (pinfunction "I/O_43") (pintype "bidirectional+no_connect"))
    )
    (net (code "104") (name "unconnected-(J31-I{slash}O-Pad55)") (class "Default")
      (node (ref "J31") (pin "55") (pinfunction "I/O_55") (pintype "bidirectional+no_connect"))
    )
    (net (code "105") (name "unconnected-(R272-Pad1)") (class "Default")
      (node (ref "R272") (pin "1") (pinfunction "1_1") (pintype "passive+no_connect"))
    )
    (net (code "106") (name "unconnected-(R273-Pad2)") (class "Default")
      (node (ref "R273") (pin "2") (pinfunction "2_2") (pintype "passive+no_connect"))
    )
    (net (code "107") (name "unconnected-(R276-Pad1)") (class "Default")
      (node (ref "R276") (pin "1") (pinfunction "1_1") (pintype "passive+no_connect"))
    )
    (net (code "108") (name "unconnected-(R277-Pad2)") (class "Default")
      (node (ref "R277") (pin "2") (pinfunction "2_2") (pintype "passive+no_connect"))
    )
    (net (code "109") (name "unconnected-(R279-Pad1)") (class "Default")
      (node (ref "R279") (pin "1") (pinfunction "1_1") (pintype "passive+no_connect"))
    )
    (net (code "110") (name "unconnected-(R281-Pad1)") (class "Default")
      (node (ref "R281") (pin "1") (pinfunction "1_1") (pintype "passive+no_connect"))
    )
    (net (code "111") (name "unconnected-(R303-Pad1)") (class "Default")
      (node (ref "R303") (pin "1") (pinfunction "1_1") (pintype "passive+no_connect"))
    )
    (net (code "112") (name "unconnected-(R305-Pad1)") (class "Default")
      (node (ref "R305") (pin "1") (pinfunction "1_1") (pintype "passive+no_connect"))
    )
  )
)
